# univ_3-7-0-x-rev3.net
KiCad netlist of a schematic drawn in EAGLE
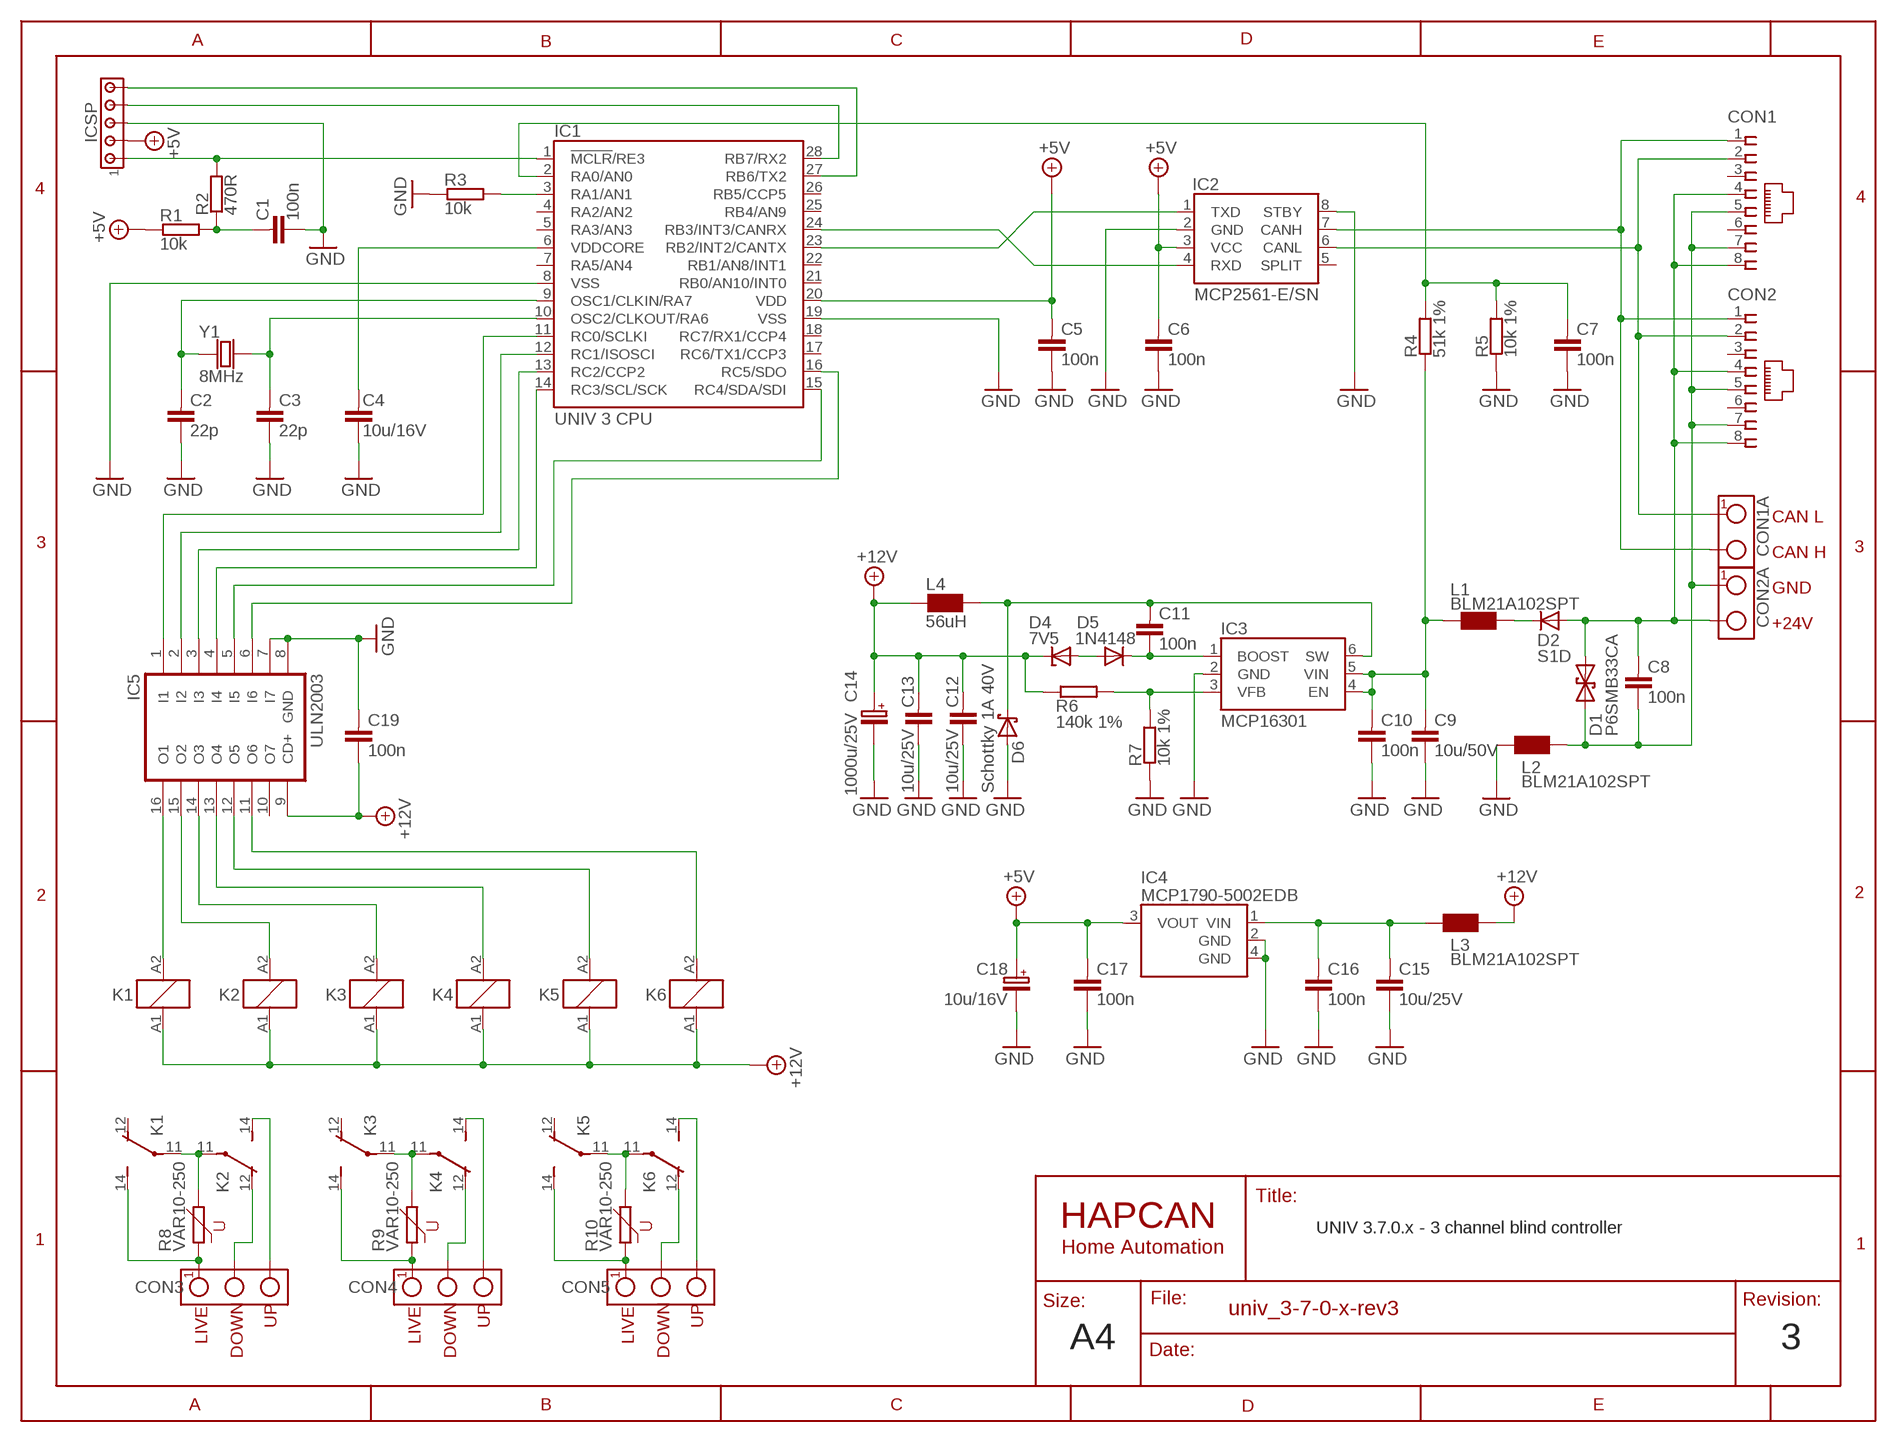
[diagram p0: schematic, sheet 1]

(export (version "E")
  (design (tool "Eeschema 10.0.6"))
  (components
    (comp (ref "C1")
      (value "100n")
      (footprint "eagle-import:0805")
      (libsource (lib "eagle-import") (part "CAPACITOR0805"))
    )
    (comp (ref "C2")
      (value "22p")
      (footprint "eagle-import:0805")
      (libsource (lib "eagle-import") (part "CAPACITOR0805"))
    )
    (comp (ref "C3")
      (value "22p")
      (footprint "eagle-import:0805")
      (libsource (lib "eagle-import") (part "CAPACITOR0805"))
    )
    (comp (ref "C4")
      (value "10u/16V")
      (footprint "eagle-import:0805")
      (libsource (lib "eagle-import") (part "CAPACITOR0805"))
    )
    (comp (ref "C5")
      (value "100n")
      (footprint "eagle-import:0805")
      (libsource (lib "eagle-import") (part "CAPACITOR0805"))
    )
    (comp (ref "C6")
      (value "100n")
      (footprint "eagle-import:0805")
      (libsource (lib "eagle-import") (part "CAPACITOR0805"))
    )
    (comp (ref "C7")
      (value "100n")
      (footprint "eagle-import:0805")
      (libsource (lib "eagle-import") (part "CAPACITOR0805"))
    )
    (comp (ref "C8")
      (value "100n")
      (footprint "eagle-import:0805")
      (libsource (lib "eagle-import") (part "CAPACITOR0805"))
    )
    (comp (ref "C9")
      (value "10u/50V")
      (footprint "eagle-import:1210")
      (libsource (lib "eagle-import") (part "CAPACITOR1210"))
    )
    (comp (ref "C10")
      (value "100n")
      (footprint "eagle-import:0805")
      (libsource (lib "eagle-import") (part "CAPACITOR0805"))
    )
    (comp (ref "C11")
      (value "100n")
      (footprint "eagle-import:0805")
      (libsource (lib "eagle-import") (part "CAPACITOR0805"))
    )
    (comp (ref "C12")
      (value "10u/25V")
      (footprint "eagle-import:1206")
      (libsource (lib "eagle-import") (part "CAPACITOR1206"))
    )
    (comp (ref "C13")
      (value "10u/25V")
      (footprint "eagle-import:1206")
      (libsource (lib "eagle-import") (part "CAPACITOR1206"))
    )
    (comp (ref "C14")
      (value "1000u/25V")
      (footprint "eagle-import:CAP-5X10.5")
      (libsource (lib "eagle-import") (part "CAPACITOR-POLARIZED-5X10.5"))
    )
    (comp (ref "C15")
      (value "10u/25V")
      (footprint "eagle-import:1206")
      (libsource (lib "eagle-import") (part "CAPACITOR1206"))
    )
    (comp (ref "C16")
      (value "100n")
      (footprint "eagle-import:0805")
      (libsource (lib "eagle-import") (part "CAPACITOR0805"))
    )
    (comp (ref "C17")
      (value "100n")
      (footprint "eagle-import:0805")
      (libsource (lib "eagle-import") (part "CAPACITOR0805"))
    )
    (comp (ref "C18")
      (value "10u/16V")
      (footprint "eagle-import:SMC_B")
      (libsource (lib "eagle-import") (part "CAPACITOR-POLARIZED-SMC_B"))
    )
    (comp (ref "C19")
      (value "100n")
      (footprint "eagle-import:0805")
      (libsource (lib "eagle-import") (part "CAPACITOR0805"))
    )
    (comp (ref "CON1")
      (value "RJ45-SOCKET")
      (footprint "eagle-import:RJ45-PCB-SOCKET")
      (libsource (lib "eagle-import") (part "RJ45-SOCKET"))
    )
    (comp (ref "CON1A")
      (value "TERMINAL-2")
      (footprint "eagle-import:ARK2-5X10,5MM")
      (libsource (lib "eagle-import") (part "TERMINAL-2-5X10,5MM"))
    )
    (comp (ref "CON2")
      (value "RJ45-SOCKET")
      (footprint "eagle-import:RJ45-PCB-SOCKET")
      (libsource (lib "eagle-import") (part "RJ45-SOCKET"))
    )
    (comp (ref "CON2A")
      (value "TERMINAL-2")
      (footprint "eagle-import:ARK2-5X10,5MM")
      (libsource (lib "eagle-import") (part "TERMINAL-2-5X10,5MM"))
    )
    (comp (ref "CON3")
      (value "TERMINAL-3-5X10.5MM")
      (footprint "eagle-import:ARK3-5X10.5MM")
      (libsource (lib "eagle-import") (part "TERMINAL-3-5X10.5MM"))
    )
    (comp (ref "CON4")
      (value "TERMINAL-3-5X10.5MM")
      (footprint "eagle-import:ARK3-5X10.5MM")
      (libsource (lib "eagle-import") (part "TERMINAL-3-5X10.5MM"))
    )
    (comp (ref "CON5")
      (value "TERMINAL-3-5X10.5MM")
      (footprint "eagle-import:ARK3-5X10.5MM")
      (libsource (lib "eagle-import") (part "TERMINAL-3-5X10.5MM"))
    )
    (comp (ref "D1")
      (value "P6SMB33CA")
      (footprint "eagle-import:DO-214_TRANSIL2")
      (libsource (lib "eagle-import") (part "DIODE_TRANSIL2"))
    )
    (comp (ref "D2")
      (value "S1D")
      (footprint "eagle-import:DO-214")
      (libsource (lib "eagle-import") (part "DIODE_DO-214"))
    )
    (comp (ref "D4")
      (value "7V5")
      (footprint "eagle-import:SOD-80")
      (libsource (lib "eagle-import") (part "DIODE_ZENER_SOD-80"))
    )
    (comp (ref "D5")
      (value "1N4148")
      (footprint "eagle-import:0805")
      (libsource (lib "eagle-import") (part "DIODE_0805"))
    )
    (comp (ref "D6")
      (value "Schottky 1A 40V")
      (footprint "eagle-import:DO-214")
      (libsource (lib "eagle-import") (part "DIODE_TRANSIL1_DO214"))
    )
    (comp (ref "IC1")
      (value "UNIV 3 CPU")
      (footprint "eagle-import:UNIV3CPU")
      (libsource (lib "eagle-import") (part "UNIV3CPU-I/SO"))
    )
    (comp (ref "IC2")
      (value "MCP2561-E/SN")
      (footprint "eagle-import:SO-08")
      (libsource (lib "eagle-import") (part "MCP2561-E/SN"))
    )
    (comp (ref "IC3")
      (value "MCP16301")
      (footprint "eagle-import:SOT-23-6")
      (libsource (lib "eagle-import") (part "MCP16301SOT23-6"))
    )
    (comp (ref "IC4")
      (value "MCP1790-5002EDB")
      (footprint "eagle-import:SOT-223")
      (libsource (lib "eagle-import") (part "MCP1826SOT223-3"))
    )
    (comp (ref "IC5")
      (value "ULN2003")
      (footprint "eagle-import:SO-16")
      (libsource (lib "eagle-import") (part "ULN2003"))
    )
    (comp (ref "ICSP")
      (value "HEADER5")
      (footprint "eagle-import:SIP-5")
      (libsource (lib "eagle-import") (part "HEADER5"))
    )
    (comp (ref "K1")
      (value "RELAY_SNR_SPDTV")
      (footprint "eagle-import:RELAY_SNR_SPDT_V")
      (libsource (lib "eagle-import") (part "RELAY_SNR_SPDTV"))
    )
    (comp (ref "K2")
      (value "RELAY_SNR_SPDTV")
      (footprint "eagle-import:RELAY_SNR_SPDT_V")
      (libsource (lib "eagle-import") (part "RELAY_SNR_SPDTV"))
    )
    (comp (ref "K3")
      (value "RELAY_SNR_SPDTV")
      (footprint "eagle-import:RELAY_SNR_SPDT_V")
      (libsource (lib "eagle-import") (part "RELAY_SNR_SPDTV"))
    )
    (comp (ref "K4")
      (value "RELAY_SNR_SPDTV")
      (footprint "eagle-import:RELAY_SNR_SPDT_V")
      (libsource (lib "eagle-import") (part "RELAY_SNR_SPDTV"))
    )
    (comp (ref "K5")
      (value "RELAY_SNR_SPDTV")
      (footprint "eagle-import:RELAY_SNR_SPDT_V")
      (libsource (lib "eagle-import") (part "RELAY_SNR_SPDTV"))
    )
    (comp (ref "K6")
      (value "RELAY_SNR_SPDTV")
      (footprint "eagle-import:RELAY_SNR_SPDT_V")
      (libsource (lib "eagle-import") (part "RELAY_SNR_SPDTV"))
    )
    (comp (ref "L1")
      (value "BLM21A102SPT")
      (footprint "eagle-import:0805")
      (libsource (lib "eagle-import") (part "CHOKE0805"))
    )
    (comp (ref "L2")
      (value "BLM21A102SPT")
      (footprint "eagle-import:0805")
      (libsource (lib "eagle-import") (part "CHOKE0805"))
    )
    (comp (ref "L3")
      (value "BLM21A102SPT")
      (footprint "eagle-import:0805")
      (libsource (lib "eagle-import") (part "CHOKE0805"))
    )
    (comp (ref "L4")
      (value "56uH")
      (footprint "eagle-import:CHOKE-DER0705")
      (libsource (lib "eagle-import") (part "CHOKEDER0705"))
    )
    (comp (ref "R1")
      (value "10k")
      (footprint "eagle-import:0805")
      (libsource (lib "eagle-import") (part "RESISTOR0805"))
    )
    (comp (ref "R2")
      (value "470R")
      (footprint "eagle-import:0805")
      (libsource (lib "eagle-import") (part "RESISTOR0805"))
    )
    (comp (ref "R3")
      (value "10k")
      (footprint "eagle-import:0805")
      (libsource (lib "eagle-import") (part "RESISTOR0805"))
    )
    (comp (ref "R4")
      (value "51k 1%")
      (footprint "eagle-import:0805")
      (libsource (lib "eagle-import") (part "RESISTOR0805"))
    )
    (comp (ref "R5")
      (value "10k 1%")
      (footprint "eagle-import:0805")
      (libsource (lib "eagle-import") (part "RESISTOR0805"))
    )
    (comp (ref "R6")
      (value "140k 1%")
      (footprint "eagle-import:0805")
      (libsource (lib "eagle-import") (part "RESISTOR0805"))
    )
    (comp (ref "R7")
      (value "10k 1%")
      (footprint "eagle-import:0805")
      (libsource (lib "eagle-import") (part "RESISTOR0805"))
    )
    (comp (ref "R8")
      (value "VAR10-250")
      (footprint "eagle-import:VARISTOR1")
      (libsource (lib "eagle-import") (part "VARISTOR7.5MM-1"))
    )
    (comp (ref "R9")
      (value "VAR10-250")
      (footprint "eagle-import:VARISTOR1")
      (libsource (lib "eagle-import") (part "VARISTOR7.5MM-1"))
    )
    (comp (ref "R10")
      (value "VAR10-250")
      (footprint "eagle-import:VARISTOR1")
      (libsource (lib "eagle-import") (part "VARISTOR7.5MM-1"))
    )
    (comp (ref "Y1")
      (value "8MHz")
      (footprint "eagle-import:CRYSTAL-HC49V")
      (libsource (lib "eagle-import") (part "CRYSTAL-HC49V"))
    )
  )
  (nets
    (net (code "1") (name "+5V") (class "Default")
      (node (ref "C17") (pin "1") (pinfunction "1_1") (pintype "passive"))
      (node (ref "C18") (pin "+") (pinfunction "1_+") (pintype "passive"))
      (node (ref "C5") (pin "1") (pinfunction "1_1") (pintype "passive"))
      (node (ref "C6") (pin "1") (pinfunction "1_1") (pintype "passive"))
      (node (ref "IC1") (pin "20") (pinfunction "VDD_20") (pintype "bidirectional"))
      (node (ref "IC2") (pin "3") (pinfunction "VCC_3") (pintype "bidirectional"))
      (node (ref "IC4") (pin "3") (pinfunction "VOUT_3") (pintype "bidirectional"))
      (node (ref "ICSP") (pin "2") (pinfunction "2_2") (pintype "passive"))
      (node (ref "R1") (pin "1") (pinfunction "1_1") (pintype "passive"))
    )
    (net (code "2") (name "+12V") (class "Default")
      (node (ref "C12") (pin "1") (pinfunction "1_1") (pintype "passive"))
      (node (ref "C13") (pin "1") (pinfunction "1_1") (pintype "passive"))
      (node (ref "C14") (pin "+") (pinfunction "1_+") (pintype "passive"))
      (node (ref "C19") (pin "2") (pinfunction "2_2") (pintype "passive"))
      (node (ref "D4") (pin "C") (pinfunction "C_C") (pintype "passive"))
      (node (ref "IC5") (pin "9") (pinfunction "CD+_9") (pintype "passive"))
      (node (ref "K1") (pin "A1") (pinfunction "1_A1") (pintype "passive"))
      (node (ref "K2") (pin "A1") (pinfunction "1_A1") (pintype "passive"))
      (node (ref "K3") (pin "A1") (pinfunction "1_A1") (pintype "passive"))
      (node (ref "K4") (pin "A1") (pinfunction "1_A1") (pintype "passive"))
      (node (ref "K5") (pin "A1") (pinfunction "1_A1") (pintype "passive"))
      (node (ref "K6") (pin "A1") (pinfunction "1_A1") (pintype "passive"))
      (node (ref "L3") (pin "2") (pinfunction "2_2") (pintype "passive"))
      (node (ref "L4") (pin "1") (pinfunction "1_1") (pintype "passive"))
      (node (ref "R6") (pin "1") (pinfunction "1_1") (pintype "passive"))
    )
    (net (code "3") (name "GND") (class "Default")
      (node (ref "C1") (pin "2") (pinfunction "2_2") (pintype "passive"))
      (node (ref "C10") (pin "2") (pinfunction "2_2") (pintype "passive"))
      (node (ref "C12") (pin "2") (pinfunction "2_2") (pintype "passive"))
      (node (ref "C13") (pin "2") (pinfunction "2_2") (pintype "passive"))
      (node (ref "C14") (pin "-") (pinfunction "2_-") (pintype "passive"))
      (node (ref "C15") (pin "2") (pinfunction "2_2") (pintype "passive"))
      (node (ref "C16") (pin "2") (pinfunction "2_2") (pintype "passive"))
      (node (ref "C17") (pin "2") (pinfunction "2_2") (pintype "passive"))
      (node (ref "C18") (pin "-") (pinfunction "2_-") (pintype "passive"))
      (node (ref "C19") (pin "1") (pinfunction "1_1") (pintype "passive"))
      (node (ref "C2") (pin "2") (pinfunction "2_2") (pintype "passive"))
      (node (ref "C3") (pin "2") (pinfunction "2_2") (pintype "passive"))
      (node (ref "C4") (pin "2") (pinfunction "2_2") (pintype "passive"))
      (node (ref "C5") (pin "2") (pinfunction "2_2") (pintype "passive"))
      (node (ref "C6") (pin "2") (pinfunction "2_2") (pintype "passive"))
      (node (ref "C7") (pin "2") (pinfunction "2_2") (pintype "passive"))
      (node (ref "C9") (pin "2") (pinfunction "2_2") (pintype "passive"))
      (node (ref "D6") (pin "A") (pinfunction "A_A") (pintype "passive"))
      (node (ref "IC1") (pin "19") (pinfunction "VSS_19") (pintype "bidirectional"))
      (node (ref "IC1") (pin "8") (pinfunction "VSS_8") (pintype "bidirectional"))
      (node (ref "IC2") (pin "2") (pinfunction "GND_2") (pintype "bidirectional"))
      (node (ref "IC2") (pin "8") (pinfunction "STBY_8") (pintype "bidirectional"))
      (node (ref "IC3") (pin "2") (pinfunction "GND_2") (pintype "bidirectional"))
      (node (ref "IC4") (pin "2") (pinfunction "GND_2") (pintype "bidirectional"))
      (node (ref "IC4") (pin "4") (pinfunction "GND_4") (pintype "bidirectional"))
      (node (ref "IC5") (pin "7") (pinfunction "I7_7") (pintype "input"))
      (node (ref "IC5") (pin "8") (pinfunction "GND_8") (pintype "power_in"))
      (node (ref "ICSP") (pin "3") (pinfunction "3_3") (pintype "passive"))
      (node (ref "L2") (pin "1") (pinfunction "1_1") (pintype "passive"))
      (node (ref "R3") (pin "1") (pinfunction "1_1") (pintype "passive"))
      (node (ref "R5") (pin "1") (pinfunction "1_1") (pintype "passive"))
      (node (ref "R7") (pin "1") (pinfunction "1_1") (pintype "passive"))
    )
    (net (code "4") (name "Net-(C1-Pad1)") (class "Default")
      (node (ref "C1") (pin "1") (pinfunction "1_1") (pintype "passive"))
      (node (ref "R1") (pin "2") (pinfunction "2_2") (pintype "passive"))
      (node (ref "R2") (pin "1") (pinfunction "1_1") (pintype "passive"))
    )
    (net (code "5") (name "Net-(D1-1)") (class "Default")
      (node (ref "C8") (pin "2") (pinfunction "2_2") (pintype "passive"))
      (node (ref "CON1") (pin "5") (pinfunction "5_5") (pintype "passive"))
      (node (ref "CON1") (pin "7") (pinfunction "7_7") (pintype "passive"))
      (node (ref "CON2") (pin "5") (pinfunction "5_5") (pintype "passive"))
      (node (ref "CON2") (pin "7") (pinfunction "7_7") (pintype "passive"))
      (node (ref "CON2A") (pin "1") (pinfunction "1_1") (pintype "passive"))
      (node (ref "D1") (pin "A") (pinfunction "1_A") (pintype "passive"))
      (node (ref "L2") (pin "2") (pinfunction "2_2") (pintype "passive"))
    )
    (net (code "6") (name "Net-(D1-2)") (class "Default")
      (node (ref "C8") (pin "1") (pinfunction "1_1") (pintype "passive"))
      (node (ref "CON1") (pin "4") (pinfunction "4_4") (pintype "passive"))
      (node (ref "CON1") (pin "8") (pinfunction "8_8") (pintype "passive"))
      (node (ref "CON2") (pin "4") (pinfunction "4_4") (pintype "passive"))
      (node (ref "CON2") (pin "8") (pinfunction "8_8") (pintype "passive"))
      (node (ref "CON2A") (pin "2") (pinfunction "2_2") (pintype "passive"))
      (node (ref "D1") (pin "C") (pinfunction "2_C") (pintype "passive"))
      (node (ref "D2") (pin "A") (pinfunction "A_A") (pintype "passive"))
    )
    (net (code "7") (name "Net-(D2-PadC)") (class "Default")
      (node (ref "D2") (pin "C") (pinfunction "C_C") (pintype "passive"))
      (node (ref "L1") (pin "2") (pinfunction "2_2") (pintype "passive"))
    )
    (net (code "8") (name "Net-(D5-A)") (class "Default")
      (node (ref "D4") (pin "A") (pinfunction "A_A") (pintype "passive"))
      (node (ref "D5") (pin "2") (pinfunction "A_2") (pintype "passive"))
    )
    (net (code "9") (name "Net-(D5-C)") (class "Default")
      (node (ref "C11") (pin "2") (pinfunction "2_2") (pintype "passive"))
      (node (ref "D5") (pin "1") (pinfunction "C_1") (pintype "passive"))
      (node (ref "IC3") (pin "1") (pinfunction "BOOST_1") (pintype "bidirectional"))
    )
    (net (code "10") (name "Net-(IC1-OSC1{slash}CLKIN{slash}RA7)") (class "Default")
      (node (ref "C2") (pin "1") (pinfunction "1_1") (pintype "passive"))
      (node (ref "IC1") (pin "9") (pinfunction "OSC1/CLKIN/RA7_9") (pintype "bidirectional"))
      (node (ref "Y1") (pin "1") (pinfunction "1_1") (pintype "passive"))
    )
    (net (code "11") (name "Net-(IC1-OSC2{slash}CLKOUT{slash}RA6)") (class "Default")
      (node (ref "C3") (pin "1") (pinfunction "1_1") (pintype "passive"))
      (node (ref "IC1") (pin "10") (pinfunction "OSC2/CLKOUT/RA6_10") (pintype "bidirectional"))
      (node (ref "Y1") (pin "2") (pinfunction "2_2") (pintype "passive"))
    )
    (net (code "12") (name "Net-(IC1-RA0{slash}AN0)") (class "Default")
      (node (ref "C7") (pin "1") (pinfunction "1_1") (pintype "passive"))
      (node (ref "IC1") (pin "2") (pinfunction "RA0/AN0_2") (pintype "bidirectional"))
      (node (ref "R4") (pin "2") (pinfunction "2_2") (pintype "passive"))
      (node (ref "R5") (pin "2") (pinfunction "2_2") (pintype "passive"))
    )
    (net (code "13") (name "Net-(IC1-RA1{slash}AN1)") (class "Default")
      (node (ref "IC1") (pin "3") (pinfunction "RA1/AN1_3") (pintype "bidirectional"))
      (node (ref "R3") (pin "2") (pinfunction "2_2") (pintype "passive"))
    )
    (net (code "14") (name "Net-(IC1-RB2{slash}INT2{slash}CANTX)") (class "Default")
      (node (ref "IC1") (pin "23") (pinfunction "RB2/INT2/CANTX_23") (pintype "bidirectional"))
      (node (ref "IC2") (pin "1") (pinfunction "TXD_1") (pintype "bidirectional"))
    )
    (net (code "15") (name "Net-(IC1-RB3{slash}INT3{slash}CANRX)") (class "Default")
      (node (ref "IC1") (pin "24") (pinfunction "RB3/INT3/CANRX_24") (pintype "bidirectional"))
      (node (ref "IC2") (pin "4") (pinfunction "RXD_4") (pintype "bidirectional"))
    )
    (net (code "16") (name "Net-(IC1-RB6{slash}TX2)") (class "Default")
      (node (ref "IC1") (pin "27") (pinfunction "RB6/TX2_27") (pintype "bidirectional"))
      (node (ref "ICSP") (pin "5") (pinfunction "5_5") (pintype "passive"))
    )
    (net (code "17") (name "Net-(IC1-RB7{slash}RX2)") (class "Default")
      (node (ref "IC1") (pin "28") (pinfunction "RB7/RX2_28") (pintype "bidirectional"))
      (node (ref "ICSP") (pin "4") (pinfunction "4_4") (pintype "passive"))
    )
    (net (code "18") (name "Net-(IC1-RC0{slash}SCLKI)") (class "Default")
      (node (ref "IC1") (pin "11") (pinfunction "RC0/SCLKI_11") (pintype "bidirectional"))
      (node (ref "IC5") (pin "1") (pinfunction "I1_1") (pintype "input"))
    )
    (net (code "19") (name "Net-(IC1-RC1{slash}ISOSCI)") (class "Default")
      (node (ref "IC1") (pin "12") (pinfunction "RC1/ISOSCI_12") (pintype "bidirectional"))
      (node (ref "IC5") (pin "2") (pinfunction "I2_2") (pintype "input"))
    )
    (net (code "20") (name "Net-(IC1-RC2{slash}CCP2)") (class "Default")
      (node (ref "IC1") (pin "13") (pinfunction "RC2/CCP2_13") (pintype "bidirectional"))
      (node (ref "IC5") (pin "3") (pinfunction "I3_3") (pintype "input"))
    )
    (net (code "21") (name "Net-(IC1-RC3{slash}SCL{slash}SCK)") (class "Default")
      (node (ref "IC1") (pin "14") (pinfunction "RC3/SCL/SCK_14") (pintype "bidirectional"))
      (node (ref "IC5") (pin "4") (pinfunction "I4_4") (pintype "input"))
    )
    (net (code "22") (name "Net-(IC1-RC4{slash}SDA{slash}SDI)") (class "Default")
      (node (ref "IC1") (pin "15") (pinfunction "RC4/SDA/SDI_15") (pintype "bidirectional"))
      (node (ref "IC5") (pin "5") (pinfunction "I5_5") (pintype "input"))
    )
    (net (code "23") (name "Net-(IC1-RC5{slash}SDO)") (class "Default")
      (node (ref "IC1") (pin "16") (pinfunction "RC5/SDO_16") (pintype "bidirectional"))
      (node (ref "IC5") (pin "6") (pinfunction "I6_6") (pintype "input"))
    )
    (net (code "24") (name "Net-(IC1-VDDCORE)") (class "Default")
      (node (ref "C4") (pin "1") (pinfunction "1_1") (pintype "passive"))
      (node (ref "IC1") (pin "6") (pinfunction "VDDCORE_6") (pintype "bidirectional"))
    )
    (net (code "25") (name "Net-(IC1-~{MCLR}{slash}RE3)") (class "Default")
      (node (ref "IC1") (pin "1") (pinfunction "~{MCLR}/RE3_1") (pintype "bidirectional"))
      (node (ref "ICSP") (pin "1") (pinfunction "1_1") (pintype "passive"))
      (node (ref "R2") (pin "2") (pinfunction "2_2") (pintype "passive"))
    )
    (net (code "26") (name "Net-(IC2-CANH)") (class "Default")
      (node (ref "CON1") (pin "1") (pinfunction "1_1") (pintype "passive"))
      (node (ref "CON1A") (pin "2") (pinfunction "2_2") (pintype "passive"))
      (node (ref "CON2") (pin "1") (pinfunction "1_1") (pintype "passive"))
      (node (ref "IC2") (pin "7") (pinfunction "CANH_7") (pintype "bidirectional"))
    )
    (net (code "27") (name "Net-(IC2-CANL)") (class "Default")
      (node (ref "CON1") (pin "2") (pinfunction "2_2") (pintype "passive"))
      (node (ref "CON1A") (pin "1") (pinfunction "1_1") (pintype "passive"))
      (node (ref "CON2") (pin "2") (pinfunction "2_2") (pintype "passive"))
      (node (ref "IC2") (pin "6") (pinfunction "CANL_6") (pintype "bidirectional"))
    )
    (net (code "28") (name "Net-(IC3-EN)") (class "Default")
      (node (ref "C10") (pin "1") (pinfunction "1_1") (pintype "passive"))
      (node (ref "C9") (pin "1") (pinfunction "1_1") (pintype "passive"))
      (node (ref "IC3") (pin "4") (pinfunction "EN_4") (pintype "bidirectional"))
      (node (ref "IC3") (pin "5") (pinfunction "VIN_5") (pintype "bidirectional"))
      (node (ref "L1") (pin "1") (pinfunction "1_1") (pintype "passive"))
      (node (ref "R4") (pin "1") (pinfunction "1_1") (pintype "passive"))
    )
    (net (code "29") (name "Net-(IC3-SW)") (class "Default")
      (node (ref "C11") (pin "1") (pinfunction "1_1") (pintype "passive"))
      (node (ref "D6") (pin "C") (pinfunction "C_C") (pintype "passive"))
      (node (ref "IC3") (pin "6") (pinfunction "SW_6") (pintype "bidirectional"))
      (node (ref "L4") (pin "2") (pinfunction "2_2") (pintype "passive"))
    )
    (net (code "30") (name "Net-(IC3-VFB)") (class "Default")
      (node (ref "IC3") (pin "3") (pinfunction "VFB_3") (pintype "bidirectional"))
      (node (ref "R6") (pin "2") (pinfunction "2_2") (pintype "passive"))
      (node (ref "R7") (pin "2") (pinfunction "2_2") (pintype "passive"))
    )
    (net (code "31") (name "Net-(IC4-VIN)") (class "Default")
      (node (ref "C15") (pin "1") (pinfunction "1_1") (pintype "passive"))
      (node (ref "C16") (pin "1") (pinfunction "1_1") (pintype "passive"))
      (node (ref "IC4") (pin "1") (pinfunction "VIN_1") (pintype "bidirectional"))
      (node (ref "L3") (pin "1") (pinfunction "1_1") (pintype "passive"))
    )
    (net (code "32") (name "Net-(IC5-O1)") (class "Default")
      (node (ref "IC5") (pin "16") (pinfunction "O1_16") (pintype "open_collector"))
      (node (ref "K1") (pin "A2") (pinfunction "2_A2") (pintype "passive"))
    )
    (net (code "33") (name "Net-(IC5-O2)") (class "Default")
      (node (ref "IC5") (pin "15") (pinfunction "O2_15") (pintype "open_collector"))
      (node (ref "K2") (pin "A2") (pinfunction "2_A2") (pintype "passive"))
    )
    (net (code "34") (name "Net-(IC5-O3)") (class "Default")
      (node (ref "IC5") (pin "14") (pinfunction "O3_14") (pintype "open_collector"))
      (node (ref "K3") (pin "A2") (pinfunction "2_A2") (pintype "passive"))
    )
    (net (code "35") (name "Net-(IC5-O4)") (class "Default")
      (node (ref "IC5") (pin "13") (pinfunction "O4_13") (pintype "open_collector"))
      (node (ref "K4") (pin "A2") (pinfunction "2_A2") (pintype "passive"))
    )
    (net (code "36") (name "Net-(IC5-O5)") (class "Default")
      (node (ref "IC5") (pin "12") (pinfunction "O5_12") (pintype "open_collector"))
      (node (ref "K5") (pin "A2") (pinfunction "2_A2") (pintype "passive"))
    )
    (net (code "37") (name "Net-(IC5-O6)") (class "Default")
      (node (ref "IC5") (pin "11") (pinfunction "O6_11") (pintype "open_collector"))
      (node (ref "K6") (pin "A2") (pinfunction "2_A2") (pintype "passive"))
    )
    (net (code "38") (name "Net-(K1B-COM)") (class "Default")
      (node (ref "K1") (pin "11") (pinfunction "COM_11") (pintype "passive"))
      (node (ref "K2") (pin "11") (pinfunction "COM_11") (pintype "passive"))
      (node (ref "R8") (pin "2") (pinfunction "2_2") (pintype "passive"))
    )
    (net (code "39") (name "Net-(K1B-NO)") (class "Default")
      (node (ref "CON3") (pin "1") (pinfunction "1_1") (pintype "passive"))
      (node (ref "K1") (pin "14") (pinfunction "NO_14") (pintype "passive"))
      (node (ref "R8") (pin "1") (pinfunction "1_1") (pintype "passive"))
    )
    (net (code "40") (name "Net-(K2B-NC)") (class "Default")
      (node (ref "CON3") (pin "2") (pinfunction "2_2") (pintype "passive"))
      (node (ref "K2") (pin "12") (pinfunction "NC_12") (pintype "passive"))
    )
    (net (code "41") (name "Net-(K2B-NO)") (class "Default")
      (node (ref "CON3") (pin "3") (pinfunction "3_3") (pintype "passive"))
      (node (ref "K2") (pin "14") (pinfunction "NO_14") (pintype "passive"))
    )
    (net (code "42") (name "Net-(K3B-COM)") (class "Default")
      (node (ref "K3") (pin "11") (pinfunction "COM_11") (pintype "passive"))
      (node (ref "K4") (pin "11") (pinfunction "COM_11") (pintype "passive"))
      (node (ref "R9") (pin "2") (pinfunction "2_2") (pintype "passive"))
    )
    (net (code "43") (name "Net-(K3B-NO)") (class "Default")
      (node (ref "CON4") (pin "1") (pinfunction "1_1") (pintype "passive"))
      (node (ref "K3") (pin "14") (pinfunction "NO_14") (pintype "passive"))
      (node (ref "R9") (pin "1") (pinfunction "1_1") (pintype "passive"))
    )
    (net (code "44") (name "Net-(K4B-NC)") (class "Default")
      (node (ref "CON4") (pin "2") (pinfunction "2_2") (pintype "passive"))
      (node (ref "K4") (pin "12") (pinfunction "NC_12") (pintype "passive"))
    )
    (net (code "45") (name "Net-(K4B-NO)") (class "Default")
      (node (ref "CON4") (pin "3") (pinfunction "3_3") (pintype "passive"))
      (node (ref "K4") (pin "14") (pinfunction "NO_14") (pintype "passive"))
    )
    (net (code "46") (name "Net-(K5B-COM)") (class "Default")
      (node (ref "K5") (pin "11") (pinfunction "COM_11") (pintype "passive"))
      (node (ref "K6") (pin "11") (pinfunction "COM_11") (pintype "passive"))
      (node (ref "R10") (pin "2") (pinfunction "2_2") (pintype "passive"))
    )
    (net (code "47") (name "Net-(K5B-NO)") (class "Default")
      (node (ref "CON5") (pin "1") (pinfunction "1_1") (pintype "passive"))
      (node (ref "K5") (pin "14") (pinfunction "NO_14") (pintype "passive"))
      (node (ref "R10") (pin "1") (pinfunction "1_1") (pintype "passive"))
    )
    (net (code "48") (name "Net-(K6B-NC)") (class "Default")
      (node (ref "CON5") (pin "2") (pinfunction "2_2") (pintype "passive"))
      (node (ref "K6") (pin "12") (pinfunction "NC_12") (pintype "passive"))
    )
    (net (code "49") (name "Net-(K6B-NO)") (class "Default")
      (node (ref "CON5") (pin "3") (pinfunction "3_3") (pintype "passive"))
      (node (ref "K6") (pin "14") (pinfunction "NO_14") (pintype "passive"))
    )
    (net (code "50") (name "unconnected-(CON1-Pad3)") (class "Default")
      (node (ref "CON1") (pin "3") (pinfunction "3_3") (pintype "passive"))
    )
    (net (code "51") (name "unconnected-(CON1-Pad6)") (class "Default")
      (node (ref "CON1") (pin "6") (pinfunction "6_6") (pintype "passive"))
    )
    (net (code "52") (name "unconnected-(CON2-Pad3)") (class "Default")
      (node (ref "CON2") (pin "3") (pinfunction "3_3") (pintype "passive"))
    )
    (net (code "53") (name "unconnected-(CON2-Pad6)") (class "Default")
      (node (ref "CON2") (pin "6") (pinfunction "6_6") (pintype "passive"))
    )
    (net (code "54") (name "unconnected-(IC1-RA2{slash}AN2-Pad4)") (class "Default")
      (node (ref "IC1") (pin "4") (pinfunction "RA2/AN2_4") (pintype "bidirectional"))
    )
    (net (code "55") (name "unconnected-(IC1-RA3{slash}AN3-Pad5)") (class "Default")
      (node (ref "IC1") (pin "5") (pinfunction "RA3/AN3_5") (pintype "bidirectional"))
    )
    (net (code "56") (name "unconnected-(IC1-RA5{slash}AN4-Pad7)") (class "Default")
      (node (ref "IC1") (pin "7") (pinfunction "RA5/AN4_7") (pintype "bidirectional"))
    )
    (net (code "57") (name "unconnected-(IC1-RB0{slash}AN10{slash}INT0-Pad21)") (class "Default")
      (node (ref "IC1") (pin "21") (pinfunction "RB0/AN10/INT0_21") (pintype "bidirectional"))
    )
    (net (code "58") (name "unconnected-(IC1-RB1{slash}AN8{slash}INT1-Pad22)") (class "Default")
      (node (ref "IC1") (pin "22") (pinfunction "RB1/AN8/INT1_22") (pintype "bidirectional"))
    )
    (net (code "59") (name "unconnected-(IC1-RB4{slash}AN9-Pad25)") (class "Default")
      (node (ref "IC1") (pin "25") (pinfunction "RB4/AN9_25") (pintype "bidirectional"))
    )
    (net (code "60") (name "unconnected-(IC1-RB5{slash}CCP5-Pad26)") (class "Default")
      (node (ref "IC1") (pin "26") (pinfunction "RB5/CCP5_26") (pintype "bidirectional"))
    )
    (net (code "61") (name "unconnected-(IC1-RC6{slash}TX1{slash}CCP3-Pad17)") (class "Default")
      (node (ref "IC1") (pin "17") (pinfunction "RC6/TX1/CCP3_17") (pintype "bidirectional"))
    )
    (net (code "62") (name "unconnected-(IC1-RC7{slash}RX1{slash}CCP4-Pad18)") (class "Default")
      (node (ref "IC1") (pin "18") (pinfunction "RC7/RX1/CCP4_18") (pintype "bidirectional"))
    )
    (net (code "63") (name "unconnected-(IC2-SPLIT-Pad5)") (class "Default")
      (node (ref "IC2") (pin "5") (pinfunction "SPLIT_5") (pintype "bidirectional"))
    )
    (net (code "64") (name "unconnected-(IC5-O7-Pad10)") (class "Default")
      (node (ref "IC5") (pin "10") (pinfunction "O7_10") (pintype "open_collector"))
    )
    (net (code "65") (name "unconnected-(K1B-NC-Pad12)") (class "Default")
      (node (ref "K1") (pin "12") (pinfunction "NC_12") (pintype "passive"))
    )
    (net (code "66") (name "unconnected-(K3B-NC-Pad12)") (class "Default")
      (node (ref "K3") (pin "12") (pinfunction "NC_12") (pintype "passive"))
    )
    (net (code "67") (name "unconnected-(K5B-NC-Pad12)") (class "Default")
      (node (ref "K5") (pin "12") (pinfunction "NC_12") (pintype "passive"))
    )
  )
)
